# VOLTAGE_MONITOR.net
KiCad netlist of a schematic drawn in Altium Designer
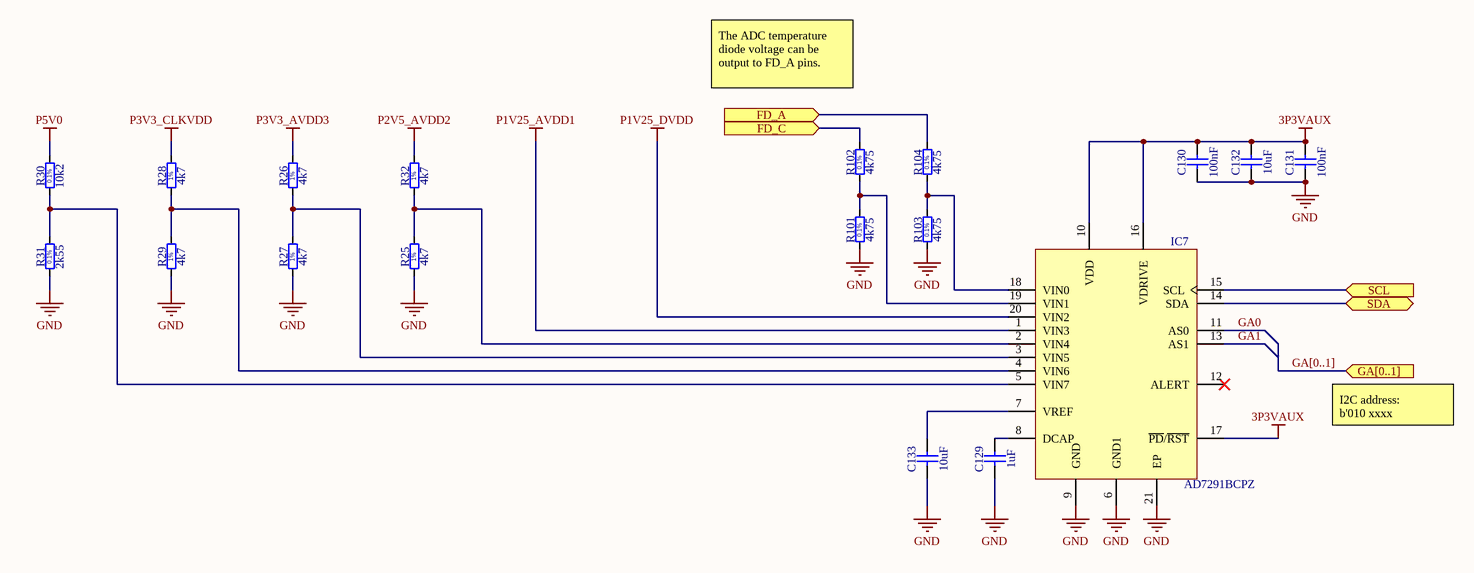
[diagram p0: VOLTAGE_MONITOR.SchDoc]

(export (version "E")
  (design (tool "Eeschema 10.0.6"))
  (components
    (comp (ref "C129")
      (value "1uF")
      (footprint "CAPC1005X55N")
      (description "Non-polarised capacitor")
      (fields
        (field (name "TOLERANCE") "±10%")
        (field (name "PART NUMBER") "CC0402_1UF_16V_10%_X5R")
        (field (name "AUTHOR") "CERN DEM JLC")
      )
      (libsource (lib "Capacitors") (part "Capacitor - non polarized"))
    )
    (comp (ref "C130")
      (value "100nF")
      (footprint "CAPC0603X33N")
      (description "Non-polarised capacitor")
      (fields
        (field (name "TOLERANCE") "±10%")
        (field (name "PART NUMBER") "CC0201_100NF_6.3V_10%_X5R")
        (field (name "AUTHOR") "CERN DEM JLC")
      )
      (libsource (lib "Capacitors") (part "Capacitor - non polarized"))
    )
    (comp (ref "C131")
      (value "100nF")
      (footprint "CAPC0603X33N")
      (description "Non-polarised capacitor")
      (fields
        (field (name "TOLERANCE") "±10%")
        (field (name "PART NUMBER") "CC0201_100NF_6.3V_10%_X5R")
        (field (name "AUTHOR") "CERN DEM JLC")
      )
      (libsource (lib "Capacitors") (part "Capacitor - non polarized"))
    )
    (comp (ref "C132")
      (value "10uF")
      (footprint "CAPC1608X87N")
      (description "Non-polarised capacitor")
      (fields
        (field (name "TOLERANCE") "±20%")
        (field (name "PART NUMBER") "CC0603_10UF_6.3V_20%_X5R")
        (field (name "AUTHOR") "CERN DEM JLC")
      )
      (libsource (lib "Capacitors") (part "Capacitor - non polarized"))
    )
    (comp (ref "C133")
      (value "10uF")
      (footprint "CAPC1608X87N")
      (description "Non-polarised capacitor")
      (fields
        (field (name "TOLERANCE") "±20%")
        (field (name "PART NUMBER") "CC0603_10UF_6.3V_20%_X5R")
        (field (name "AUTHOR") "CERN DEM JLC")
      )
      (libsource (lib "Capacitors") (part "Capacitor - non polarized"))
    )
    (comp (ref "IC7")
      (value "AD7291BCPZ")
      (footprint "CP_20_8")
      (description "8-Channel, I2C, 12-Bit SAR ADC with Temperature Sensor")
      (fields (field (name "GENERIC PART NUMBER") "AD7291") (field (name "MANUFACTURER") "Analog Devices"))
      (libsource (lib "FMC_ADC") (part "AD7291BCPZ"))
    )
    (comp (ref "R25")
      (value "4k7")
      (footprint "RESC1005X40N")
      (description "Resistor - 1%")
      (fields
        (field (name "POWER") "0.0625W")
        (field (name "TOLERANCE") "±1%")
        (field (name "AUTHOR") "CERN DEM JLC")
      )
      (libsource (lib "Resistors") (part "Resistor - 1%"))
    )
    (comp (ref "R26")
      (value "4k7")
      (footprint "RESC1005X40N")
      (description "Resistor - 1%")
      (fields
        (field (name "POWER") "0.0625W")
        (field (name "TOLERANCE") "±1%")
        (field (name "AUTHOR") "CERN DEM JLC")
      )
      (libsource (lib "Resistors") (part "Resistor - 1%"))
    )
    (comp (ref "R27")
      (value "4k7")
      (footprint "RESC1005X40N")
      (description "Resistor - 1%")
      (fields
        (field (name "POWER") "0.0625W")
        (field (name "TOLERANCE") "±1%")
        (field (name "AUTHOR") "CERN DEM JLC")
      )
      (libsource (lib "Resistors") (part "Resistor - 1%"))
    )
    (comp (ref "R28")
      (value "4k7")
      (footprint "RESC1005X40N")
      (description "Resistor - 1%")
      (fields
        (field (name "POWER") "0.0625W")
        (field (name "TOLERANCE") "±1%")
        (field (name "AUTHOR") "CERN DEM JLC")
      )
      (libsource (lib "Resistors") (part "Resistor - 1%"))
    )
    (comp (ref "R29")
      (value "4k7")
      (footprint "RESC1005X40N")
      (description "Resistor - 1%")
      (fields
        (field (name "POWER") "0.0625W")
        (field (name "TOLERANCE") "±1%")
        (field (name "AUTHOR") "CERN DEM JLC")
      )
      (libsource (lib "Resistors") (part "Resistor - 1%"))
    )
    (comp (ref "R30")
      (value "10k2")
      (footprint "RESC1608X55N")
      (description "Resistor - 0.1%")
      (fields
        (field (name "PART NUMBER") "R0603_10K2_0.1%_0.063W_10PPM")
        (field (name "POWER") "0.063W")
        (field (name "AUTHOR") "CERN DEM JLC")
      )
      (libsource (lib "Resistors") (part "Resistor - 0.1%"))
    )
    (comp (ref "R31")
      (value "2k55")
      (footprint "RESC1608X55N")
      (description "Resistor - 0.1%")
      (fields
        (field (name "PART NUMBER") "R0603_2K55_0.1%_0.063W_10PPM")
        (field (name "POWER") "0.063W")
        (field (name "AUTHOR") "CERN DEM JLC")
      )
      (libsource (lib "Resistors") (part "Resistor - 0.1%"))
    )
    (comp (ref "R32")
      (value "4k7")
      (footprint "RESC1005X40N")
      (description "Resistor - 1%")
      (fields
        (field (name "POWER") "0.0625W")
        (field (name "TOLERANCE") "±1%")
        (field (name "AUTHOR") "CERN DEM JLC")
      )
      (libsource (lib "Resistors") (part "Resistor - 1%"))
    )
    (comp (ref "R101")
      (value "4k75")
      (footprint "RESC1005X35N")
      (description "Resistor - 0.1%")
      (fields
        (field (name "PART NUMBER") "R0402_4K75_0.1%_0.063W_25PPM")
        (field (name "POWER") "0.063W")
        (field (name "AUTHOR") "CERN DEM JMW")
      )
      (libsource (lib "Resistors") (part "Resistor - 0.1%"))
    )
    (comp (ref "R102")
      (value "4k75")
      (footprint "RESC1005X35N")
      (description "Resistor - 0.1%")
      (fields
        (field (name "PART NUMBER") "R0402_4K75_0.1%_0.063W_25PPM")
        (field (name "POWER") "0.063W")
        (field (name "AUTHOR") "CERN DEM JMW")
      )
      (libsource (lib "Resistors") (part "Resistor - 0.1%"))
    )
    (comp (ref "R103")
      (value "4k75")
      (footprint "RESC1005X35N")
      (description "Resistor - 0.1%")
      (fields
        (field (name "PART NUMBER") "R0402_4K75_0.1%_0.063W_25PPM")
        (field (name "POWER") "0.063W")
        (field (name "AUTHOR") "CERN DEM JMW")
      )
      (libsource (lib "Resistors") (part "Resistor - 0.1%"))
    )
    (comp (ref "R104")
      (value "4k75")
      (footprint "RESC1005X35N")
      (description "Resistor - 0.1%")
      (fields
        (field (name "PART NUMBER") "R0402_4K75_0.1%_0.063W_25PPM")
        (field (name "POWER") "0.063W")
        (field (name "AUTHOR") "CERN DEM JMW")
      )
      (libsource (lib "Resistors") (part "Resistor - 0.1%"))
    )
  )
  (nets
    (net (code "1") (name "/FD_A") (class "Default")
      (node (ref "R104") (pin "2") (pinfunction "2_2") (pintype "passive"))
    )
    (net (code "2") (name "/FD_C") (class "Default")
      (node (ref "R102") (pin "2") (pinfunction "2_2") (pintype "passive"))
    )
    (net (code "3") (name "/GA0") (class "Default")
      (node (ref "IC7") (pin "11") (pinfunction "AS0_11") (pintype "passive"))
    )
    (net (code "4") (name "/GA1") (class "Default")
      (node (ref "IC7") (pin "13") (pinfunction "AS1_13") (pintype "passive"))
    )
    (net (code "6") (name "/SCL") (class "Default")
      (node (ref "IC7") (pin "15") (pinfunction "SCL_15") (pintype "passive"))
    )
    (net (code "7") (name "/SDA") (class "Default")
      (node (ref "IC7") (pin "14") (pinfunction "SDA_14") (pintype "passive"))
    )
    (net (code "8") (name "3P3VAUX") (class "Default")
      (node (ref "C130") (pin "2") (pinfunction "2_2") (pintype "passive"))
      (node (ref "C131") (pin "2") (pinfunction "2_2") (pintype "passive"))
      (node (ref "C132") (pin "2") (pinfunction "2_2") (pintype "passive"))
      (node (ref "IC7") (pin "10") (pinfunction "VDD_10") (pintype "power_in"))
      (node (ref "IC7") (pin "16") (pinfunction "VDRIVE_16") (pintype "power_in"))
      (node (ref "IC7") (pin "17") (pinfunction "~{PD}/~{RST}_17") (pintype "passive"))
    )
    (net (code "9") (name "GND") (class "Default")
      (node (ref "C129") (pin "1") (pinfunction "1_1") (pintype "passive"))
      (node (ref "C130") (pin "1") (pinfunction "1_1") (pintype "passive"))
      (node (ref "C131") (pin "1") (pinfunction "1_1") (pintype "passive"))
      (node (ref "C132") (pin "1") (pinfunction "1_1") (pintype "passive"))
      (node (ref "C133") (pin "1") (pinfunction "1_1") (pintype "passive"))
      (node (ref "IC7") (pin "21") (pinfunction "EP_21") (pintype "power_in"))
      (node (ref "IC7") (pin "6") (pinfunction "GND1_6") (pintype "power_in"))
      (node (ref "IC7") (pin "9") (pinfunction "GND_9") (pintype "power_in"))
      (node (ref "R101") (pin "1") (pinfunction "1_1") (pintype "passive"))
      (node (ref "R103") (pin "1") (pinfunction "1_1") (pintype "passive"))
      (node (ref "R25") (pin "1") (pinfunction "1_1") (pintype "passive"))
      (node (ref "R27") (pin "1") (pinfunction "1_1") (pintype "passive"))
      (node (ref "R29") (pin "1") (pinfunction "1_1") (pintype "passive"))
      (node (ref "R31") (pin "1") (pinfunction "1_1") (pintype "passive"))
    )
    (net (code "10") (name "Net-(IC7-DCAP)") (class "Default")
      (node (ref "C129") (pin "2") (pinfunction "2_2") (pintype "passive"))
      (node (ref "IC7") (pin "8") (pinfunction "DCAP_8") (pintype "passive"))
    )
    (net (code "11") (name "Net-(IC7-VIN0)") (class "Default")
      (node (ref "IC7") (pin "18") (pinfunction "VIN0_18") (pintype "passive"))
      (node (ref "R103") (pin "2") (pinfunction "2_2") (pintype "passive"))
      (node (ref "R104") (pin "1") (pinfunction "1_1") (pintype "passive"))
    )
    (net (code "12") (name "Net-(IC7-VIN1)") (class "Default")
      (node (ref "IC7") (pin "19") (pinfunction "VIN1_19") (pintype "passive"))
      (node (ref "R101") (pin "2") (pinfunction "2_2") (pintype "passive"))
      (node (ref "R102") (pin "1") (pinfunction "1_1") (pintype "passive"))
    )
    (net (code "13") (name "Net-(IC7-VIN4)") (class "Default")
      (node (ref "IC7") (pin "2") (pinfunction "VIN4_2") (pintype "passive"))
      (node (ref "R25") (pin "2") (pinfunction "2_2") (pintype "passive"))
      (node (ref "R32") (pin "1") (pinfunction "1_1") (pintype "passive"))
    )
    (net (code "14") (name "Net-(IC7-VIN5)") (class "Default")
      (node (ref "IC7") (pin "3") (pinfunction "VIN5_3") (pintype "passive"))
      (node (ref "R26") (pin "1") (pinfunction "1_1") (pintype "passive"))
      (node (ref "R27") (pin "2") (pinfunction "2_2") (pintype "passive"))
    )
    (net (code "15") (name "Net-(IC7-VIN6)") (class "Default")
      (node (ref "IC7") (pin "4") (pinfunction "VIN6_4") (pintype "passive"))
      (node (ref "R28") (pin "1") (pinfunction "1_1") (pintype "passive"))
      (node (ref "R29") (pin "2") (pinfunction "2_2") (pintype "passive"))
    )
    (net (code "16") (name "Net-(IC7-VIN7)") (class "Default")
      (node (ref "IC7") (pin "5") (pinfunction "VIN7_5") (pintype "passive"))
      (node (ref "R30") (pin "1") (pinfunction "1_1") (pintype "passive"))
      (node (ref "R31") (pin "2") (pinfunction "2_2") (pintype "passive"))
    )
    (net (code "17") (name "Net-(IC7-VREF)") (class "Default")
      (node (ref "C133") (pin "2") (pinfunction "2_2") (pintype "passive"))
      (node (ref "IC7") (pin "7") (pinfunction "VREF_7") (pintype "passive"))
    )
    (net (code "18") (name "P1V25_AVDD1") (class "Default")
      (node (ref "IC7") (pin "1") (pinfunction "VIN3_1") (pintype "passive"))
    )
    (net (code "19") (name "P1V25_DVDD") (class "Default")
      (node (ref "IC7") (pin "20") (pinfunction "VIN2_20") (pintype "passive"))
    )
    (net (code "20") (name "P2V5_AVDD2") (class "Default")
      (node (ref "R32") (pin "2") (pinfunction "2_2") (pintype "passive"))
    )
    (net (code "21") (name "P3V3_AVDD3") (class "Default")
      (node (ref "R26") (pin "2") (pinfunction "2_2") (pintype "passive"))
    )
    (net (code "22") (name "P3V3_CLKVDD") (class "Default")
      (node (ref "R28") (pin "2") (pinfunction "2_2") (pintype "passive"))
    )
    (net (code "23") (name "P5V0") (class "Default")
      (node (ref "R30") (pin "2") (pinfunction "2_2") (pintype "passive"))
    )
    (net (code "24") (name "unconnected-(IC7-ALERT-Pad12)") (class "Default")
      (node (ref "IC7") (pin "12") (pinfunction "ALERT_12") (pintype "passive+no_connect"))
    )
  )
)
